# usb_light.net
KiCad netlist of a schematic drawn in EAGLE
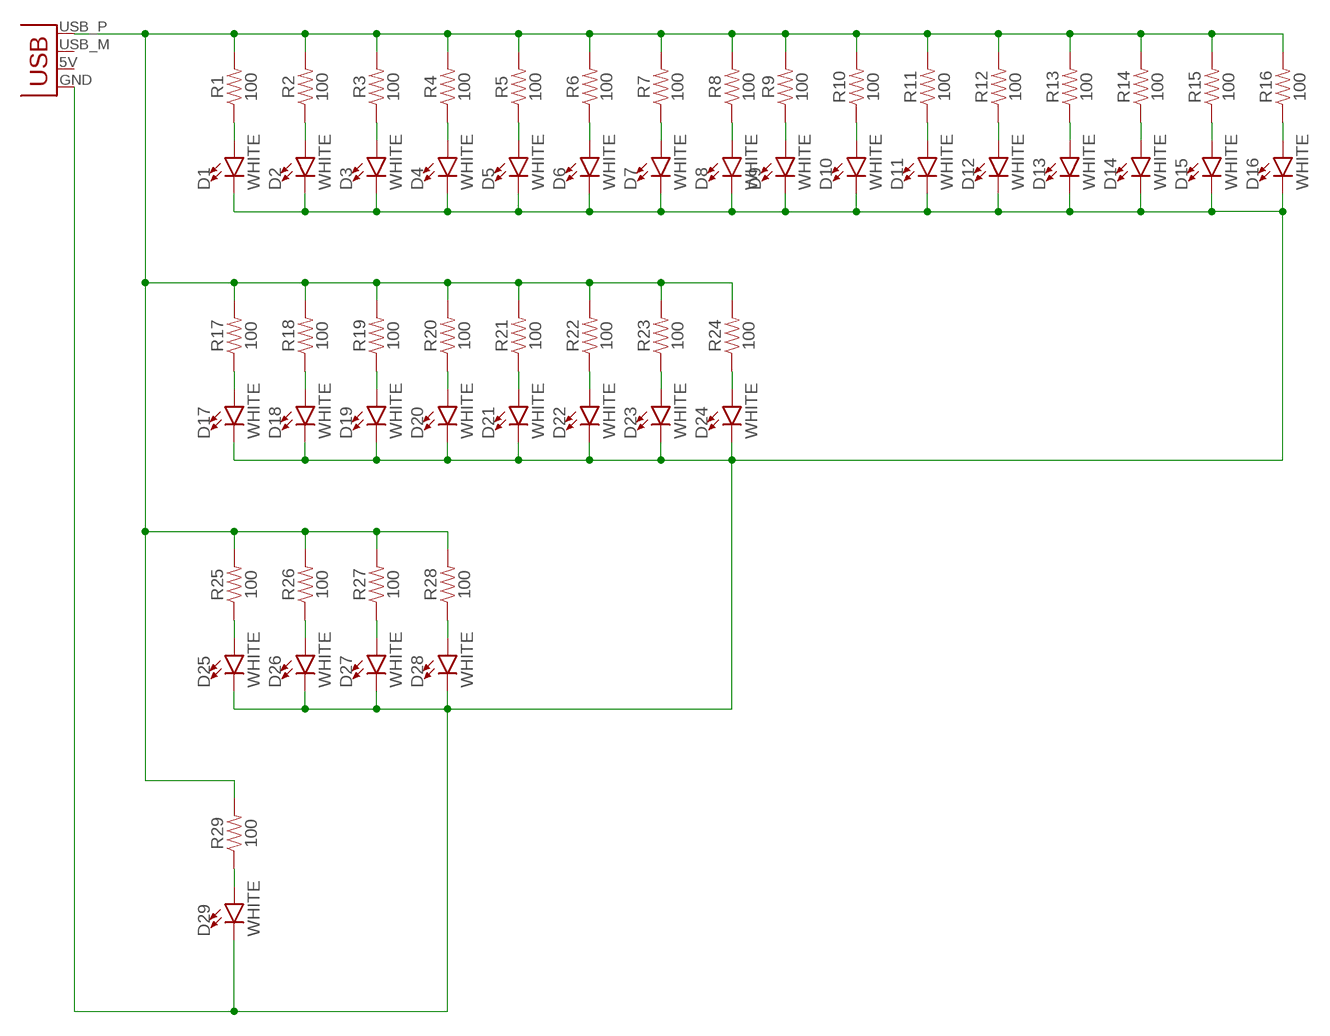
[diagram p0: schematic, sheet 1]

(export (version "E")
  (design (tool "Eeschema 10.0.6"))
  (components
    (comp (ref "D1")
      (value "WHITE")
      (footprint "eagle-import:LED-1206")
      (libsource (lib "eagle-import") (part "LED-WHITE1206"))
    )
    (comp (ref "D2")
      (value "WHITE")
      (footprint "eagle-import:LED-1206")
      (libsource (lib "eagle-import") (part "LED-WHITE1206"))
    )
    (comp (ref "D3")
      (value "WHITE")
      (footprint "eagle-import:LED-1206")
      (libsource (lib "eagle-import") (part "LED-WHITE1206"))
    )
    (comp (ref "D4")
      (value "WHITE")
      (footprint "eagle-import:LED-1206")
      (libsource (lib "eagle-import") (part "LED-WHITE1206"))
    )
    (comp (ref "D5")
      (value "WHITE")
      (footprint "eagle-import:LED-1206")
      (libsource (lib "eagle-import") (part "LED-WHITE1206"))
    )
    (comp (ref "D6")
      (value "WHITE")
      (footprint "eagle-import:LED-1206")
      (libsource (lib "eagle-import") (part "LED-WHITE1206"))
    )
    (comp (ref "D7")
      (value "WHITE")
      (footprint "eagle-import:LED-1206")
      (libsource (lib "eagle-import") (part "LED-WHITE1206"))
    )
    (comp (ref "D8")
      (value "WHITE")
      (footprint "eagle-import:LED-1206")
      (libsource (lib "eagle-import") (part "LED-WHITE1206"))
    )
    (comp (ref "D9")
      (value "WHITE")
      (footprint "eagle-import:LED-1206")
      (libsource (lib "eagle-import") (part "LED-WHITE1206"))
    )
    (comp (ref "D10")
      (value "WHITE")
      (footprint "eagle-import:LED-1206")
      (libsource (lib "eagle-import") (part "LED-WHITE1206"))
    )
    (comp (ref "D11")
      (value "WHITE")
      (footprint "eagle-import:LED-1206")
      (libsource (lib "eagle-import") (part "LED-WHITE1206"))
    )
    (comp (ref "D12")
      (value "WHITE")
      (footprint "eagle-import:LED-1206")
      (libsource (lib "eagle-import") (part "LED-WHITE1206"))
    )
    (comp (ref "D13")
      (value "WHITE")
      (footprint "eagle-import:LED-1206")
      (libsource (lib "eagle-import") (part "LED-WHITE1206"))
    )
    (comp (ref "D14")
      (value "WHITE")
      (footprint "eagle-import:LED-1206")
      (libsource (lib "eagle-import") (part "LED-WHITE1206"))
    )
    (comp (ref "D15")
      (value "WHITE")
      (footprint "eagle-import:LED-1206")
      (libsource (lib "eagle-import") (part "LED-WHITE1206"))
    )
    (comp (ref "D16")
      (value "WHITE")
      (footprint "eagle-import:LED-1206")
      (libsource (lib "eagle-import") (part "LED-WHITE1206"))
    )
    (comp (ref "D17")
      (value "WHITE")
      (footprint "eagle-import:LED-1206")
      (libsource (lib "eagle-import") (part "LED-WHITE1206"))
    )
    (comp (ref "D18")
      (value "WHITE")
      (footprint "eagle-import:LED-1206")
      (libsource (lib "eagle-import") (part "LED-WHITE1206"))
    )
    (comp (ref "D19")
      (value "WHITE")
      (footprint "eagle-import:LED-1206")
      (libsource (lib "eagle-import") (part "LED-WHITE1206"))
    )
    (comp (ref "D20")
      (value "WHITE")
      (footprint "eagle-import:LED-1206")
      (libsource (lib "eagle-import") (part "LED-WHITE1206"))
    )
    (comp (ref "D21")
      (value "WHITE")
      (footprint "eagle-import:LED-1206")
      (libsource (lib "eagle-import") (part "LED-WHITE1206"))
    )
    (comp (ref "D22")
      (value "WHITE")
      (footprint "eagle-import:LED-1206")
      (libsource (lib "eagle-import") (part "LED-WHITE1206"))
    )
    (comp (ref "D23")
      (value "WHITE")
      (footprint "eagle-import:LED-1206")
      (libsource (lib "eagle-import") (part "LED-WHITE1206"))
    )
    (comp (ref "D24")
      (value "WHITE")
      (footprint "eagle-import:LED-1206")
      (libsource (lib "eagle-import") (part "LED-WHITE1206"))
    )
    (comp (ref "D25")
      (value "WHITE")
      (footprint "eagle-import:LED-1206")
      (libsource (lib "eagle-import") (part "LED-WHITE1206"))
    )
    (comp (ref "D26")
      (value "WHITE")
      (footprint "eagle-import:LED-1206")
      (libsource (lib "eagle-import") (part "LED-WHITE1206"))
    )
    (comp (ref "D27")
      (value "WHITE")
      (footprint "eagle-import:LED-1206")
      (libsource (lib "eagle-import") (part "LED-WHITE1206"))
    )
    (comp (ref "D28")
      (value "WHITE")
      (footprint "eagle-import:LED-1206")
      (libsource (lib "eagle-import") (part "LED-WHITE1206"))
    )
    (comp (ref "D29")
      (value "WHITE")
      (footprint "eagle-import:LED-1206")
      (libsource (lib "eagle-import") (part "LED-WHITE1206"))
    )
    (comp (ref "R1")
      (value "100")
      (footprint "eagle-import:1206")
      (libsource (lib "eagle-import") (part "RESISTOR1206"))
    )
    (comp (ref "R2")
      (value "100")
      (footprint "eagle-import:1206")
      (libsource (lib "eagle-import") (part "RESISTOR1206"))
    )
    (comp (ref "R3")
      (value "100")
      (footprint "eagle-import:1206")
      (libsource (lib "eagle-import") (part "RESISTOR1206"))
    )
    (comp (ref "R4")
      (value "100")
      (footprint "eagle-import:1206")
      (libsource (lib "eagle-import") (part "RESISTOR1206"))
    )
    (comp (ref "R5")
      (value "100")
      (footprint "eagle-import:1206")
      (libsource (lib "eagle-import") (part "RESISTOR1206"))
    )
    (comp (ref "R6")
      (value "100")
      (footprint "eagle-import:1206")
      (libsource (lib "eagle-import") (part "RESISTOR1206"))
    )
    (comp (ref "R7")
      (value "100")
      (footprint "eagle-import:1206")
      (libsource (lib "eagle-import") (part "RESISTOR1206"))
    )
    (comp (ref "R8")
      (value "100")
      (footprint "eagle-import:1206")
      (libsource (lib "eagle-import") (part "RESISTOR1206"))
    )
    (comp (ref "R9")
      (value "100")
      (footprint "eagle-import:1206")
      (libsource (lib "eagle-import") (part "RESISTOR1206"))
    )
    (comp (ref "R10")
      (value "100")
      (footprint "eagle-import:1206")
      (libsource (lib "eagle-import") (part "RESISTOR1206"))
    )
    (comp (ref "R11")
      (value "100")
      (footprint "eagle-import:1206")
      (libsource (lib "eagle-import") (part "RESISTOR1206"))
    )
    (comp (ref "R12")
      (value "100")
      (footprint "eagle-import:1206")
      (libsource (lib "eagle-import") (part "RESISTOR1206"))
    )
    (comp (ref "R13")
      (value "100")
      (footprint "eagle-import:1206")
      (libsource (lib "eagle-import") (part "RESISTOR1206"))
    )
    (comp (ref "R14")
      (value "100")
      (footprint "eagle-import:1206")
      (libsource (lib "eagle-import") (part "RESISTOR1206"))
    )
    (comp (ref "R15")
      (value "100")
      (footprint "eagle-import:1206")
      (libsource (lib "eagle-import") (part "RESISTOR1206"))
    )
    (comp (ref "R16")
      (value "100")
      (footprint "eagle-import:1206")
      (libsource (lib "eagle-import") (part "RESISTOR1206"))
    )
    (comp (ref "R17")
      (value "100")
      (footprint "eagle-import:1206")
      (libsource (lib "eagle-import") (part "RESISTOR1206"))
    )
    (comp (ref "R18")
      (value "100")
      (footprint "eagle-import:1206")
      (libsource (lib "eagle-import") (part "RESISTOR1206"))
    )
    (comp (ref "R19")
      (value "100")
      (footprint "eagle-import:1206")
      (libsource (lib "eagle-import") (part "RESISTOR1206"))
    )
    (comp (ref "R20")
      (value "100")
      (footprint "eagle-import:1206")
      (libsource (lib "eagle-import") (part "RESISTOR1206"))
    )
    (comp (ref "R21")
      (value "100")
      (footprint "eagle-import:1206")
      (libsource (lib "eagle-import") (part "RESISTOR1206"))
    )
    (comp (ref "R22")
      (value "100")
      (footprint "eagle-import:1206")
      (libsource (lib "eagle-import") (part "RESISTOR1206"))
    )
    (comp (ref "R23")
      (value "100")
      (footprint "eagle-import:1206")
      (libsource (lib "eagle-import") (part "RESISTOR1206"))
    )
    (comp (ref "R24")
      (value "100")
      (footprint "eagle-import:1206")
      (libsource (lib "eagle-import") (part "RESISTOR1206"))
    )
    (comp (ref "R25")
      (value "100")
      (footprint "eagle-import:1206")
      (libsource (lib "eagle-import") (part "RESISTOR1206"))
    )
    (comp (ref "R26")
      (value "100")
      (footprint "eagle-import:1206")
      (libsource (lib "eagle-import") (part "RESISTOR1206"))
    )
    (comp (ref "R27")
      (value "100")
      (footprint "eagle-import:1206")
      (libsource (lib "eagle-import") (part "RESISTOR1206"))
    )
    (comp (ref "R28")
      (value "100")
      (footprint "eagle-import:1206")
      (libsource (lib "eagle-import") (part "RESISTOR1206"))
    )
    (comp (ref "R29")
      (value "100")
      (footprint "eagle-import:1206")
      (libsource (lib "eagle-import") (part "RESISTOR1206"))
    )
    (comp (ref "USB")
      (value "USBPCB")
      (footprint "eagle-import:USB-A-PCB")
      (libsource (lib "eagle-import") (part "USBPCB"))
    )
  )
  (nets
    (net (code "1") (name "Net-(D1-PadA)") (class "Default")
      (node (ref "D1") (pin "A") (pinfunction "A_A") (pintype "passive"))
      (node (ref "R1") (pin "1") (pinfunction "1_1") (pintype "passive"))
    )
    (net (code "2") (name "Net-(D1-PadC)") (class "Default")
      (node (ref "D1") (pin "C") (pinfunction "C_C") (pintype "passive"))
      (node (ref "D10") (pin "C") (pinfunction "C_C") (pintype "passive"))
      (node (ref "D11") (pin "C") (pinfunction "C_C") (pintype "passive"))
      (node (ref "D12") (pin "C") (pinfunction "C_C") (pintype "passive"))
      (node (ref "D13") (pin "C") (pinfunction "C_C") (pintype "passive"))
      (node (ref "D14") (pin "C") (pinfunction "C_C") (pintype "passive"))
      (node (ref "D15") (pin "C") (pinfunction "C_C") (pintype "passive"))
      (node (ref "D16") (pin "C") (pinfunction "C_C") (pintype "passive"))
      (node (ref "D17") (pin "C") (pinfunction "C_C") (pintype "passive"))
      (node (ref "D18") (pin "C") (pinfunction "C_C") (pintype "passive"))
      (node (ref "D19") (pin "C") (pinfunction "C_C") (pintype "passive"))
      (node (ref "D2") (pin "C") (pinfunction "C_C") (pintype "passive"))
      (node (ref "D20") (pin "C") (pinfunction "C_C") (pintype "passive"))
      (node (ref "D21") (pin "C") (pinfunction "C_C") (pintype "passive"))
      (node (ref "D22") (pin "C") (pinfunction "C_C") (pintype "passive"))
      (node (ref "D23") (pin "C") (pinfunction "C_C") (pintype "passive"))
      (node (ref "D24") (pin "C") (pinfunction "C_C") (pintype "passive"))
      (node (ref "D25") (pin "C") (pinfunction "C_C") (pintype "passive"))
      (node (ref "D26") (pin "C") (pinfunction "C_C") (pintype "passive"))
      (node (ref "D27") (pin "C") (pinfunction "C_C") (pintype "passive"))
      (node (ref "D28") (pin "C") (pinfunction "C_C") (pintype "passive"))
      (node (ref "D29") (pin "C") (pinfunction "C_C") (pintype "passive"))
      (node (ref "D3") (pin "C") (pinfunction "C_C") (pintype "passive"))
      (node (ref "D4") (pin "C") (pinfunction "C_C") (pintype "passive"))
      (node (ref "D5") (pin "C") (pinfunction "C_C") (pintype "passive"))
      (node (ref "D6") (pin "C") (pinfunction "C_C") (pintype "passive"))
      (node (ref "D7") (pin "C") (pinfunction "C_C") (pintype "passive"))
      (node (ref "D8") (pin "C") (pinfunction "C_C") (pintype "passive"))
      (node (ref "D9") (pin "C") (pinfunction "C_C") (pintype "passive"))
      (node (ref "USB") (pin "GND") (pinfunction "GND_GND") (pintype "bidirectional"))
    )
    (net (code "3") (name "Net-(D2-PadA)") (class "Default")
      (node (ref "D2") (pin "A") (pinfunction "A_A") (pintype "passive"))
      (node (ref "R2") (pin "1") (pinfunction "1_1") (pintype "passive"))
    )
    (net (code "4") (name "Net-(D3-PadA)") (class "Default")
      (node (ref "D3") (pin "A") (pinfunction "A_A") (pintype "passive"))
      (node (ref "R3") (pin "1") (pinfunction "1_1") (pintype "passive"))
    )
    (net (code "5") (name "Net-(D4-PadA)") (class "Default")
      (node (ref "D4") (pin "A") (pinfunction "A_A") (pintype "passive"))
      (node (ref "R4") (pin "1") (pinfunction "1_1") (pintype "passive"))
    )
    (net (code "6") (name "Net-(D5-PadA)") (class "Default")
      (node (ref "D5") (pin "A") (pinfunction "A_A") (pintype "passive"))
      (node (ref "R5") (pin "1") (pinfunction "1_1") (pintype "passive"))
    )
    (net (code "7") (name "Net-(D6-PadA)") (class "Default")
      (node (ref "D6") (pin "A") (pinfunction "A_A") (pintype "passive"))
      (node (ref "R6") (pin "1") (pinfunction "1_1") (pintype "passive"))
    )
    (net (code "8") (name "Net-(D7-PadA)") (class "Default")
      (node (ref "D7") (pin "A") (pinfunction "A_A") (pintype "passive"))
      (node (ref "R7") (pin "1") (pinfunction "1_1") (pintype "passive"))
    )
    (net (code "9") (name "Net-(D8-PadA)") (class "Default")
      (node (ref "D8") (pin "A") (pinfunction "A_A") (pintype "passive"))
      (node (ref "R8") (pin "1") (pinfunction "1_1") (pintype "passive"))
    )
    (net (code "10") (name "Net-(D9-PadA)") (class "Default")
      (node (ref "D9") (pin "A") (pinfunction "A_A") (pintype "passive"))
      (node (ref "R9") (pin "1") (pinfunction "1_1") (pintype "passive"))
    )
    (net (code "11") (name "Net-(D10-PadA)") (class "Default")
      (node (ref "D10") (pin "A") (pinfunction "A_A") (pintype "passive"))
      (node (ref "R10") (pin "1") (pinfunction "1_1") (pintype "passive"))
    )
    (net (code "12") (name "Net-(D11-PadA)") (class "Default")
      (node (ref "D11") (pin "A") (pinfunction "A_A") (pintype "passive"))
      (node (ref "R11") (pin "1") (pinfunction "1_1") (pintype "passive"))
    )
    (net (code "13") (name "Net-(D12-PadA)") (class "Default")
      (node (ref "D12") (pin "A") (pinfunction "A_A") (pintype "passive"))
      (node (ref "R12") (pin "1") (pinfunction "1_1") (pintype "passive"))
    )
    (net (code "14") (name "Net-(D13-PadA)") (class "Default")
      (node (ref "D13") (pin "A") (pinfunction "A_A") (pintype "passive"))
      (node (ref "R13") (pin "1") (pinfunction "1_1") (pintype "passive"))
    )
    (net (code "15") (name "Net-(D14-PadA)") (class "Default")
      (node (ref "D14") (pin "A") (pinfunction "A_A") (pintype "passive"))
      (node (ref "R14") (pin "1") (pinfunction "1_1") (pintype "passive"))
    )
    (net (code "16") (name "Net-(D15-PadA)") (class "Default")
      (node (ref "D15") (pin "A") (pinfunction "A_A") (pintype "passive"))
      (node (ref "R15") (pin "1") (pinfunction "1_1") (pintype "passive"))
    )
    (net (code "17") (name "Net-(D16-PadA)") (class "Default")
      (node (ref "D16") (pin "A") (pinfunction "A_A") (pintype "passive"))
      (node (ref "R16") (pin "1") (pinfunction "1_1") (pintype "passive"))
    )
    (net (code "18") (name "Net-(D17-PadA)") (class "Default")
      (node (ref "D17") (pin "A") (pinfunction "A_A") (pintype "passive"))
      (node (ref "R17") (pin "1") (pinfunction "1_1") (pintype "passive"))
    )
    (net (code "19") (name "Net-(D18-PadA)") (class "Default")
      (node (ref "D18") (pin "A") (pinfunction "A_A") (pintype "passive"))
      (node (ref "R18") (pin "1") (pinfunction "1_1") (pintype "passive"))
    )
    (net (code "20") (name "Net-(D19-PadA)") (class "Default")
      (node (ref "D19") (pin "A") (pinfunction "A_A") (pintype "passive"))
      (node (ref "R19") (pin "1") (pinfunction "1_1") (pintype "passive"))
    )
    (net (code "21") (name "Net-(D20-PadA)") (class "Default")
      (node (ref "D20") (pin "A") (pinfunction "A_A") (pintype "passive"))
      (node (ref "R20") (pin "1") (pinfunction "1_1") (pintype "passive"))
    )
    (net (code "22") (name "Net-(D21-PadA)") (class "Default")
      (node (ref "D21") (pin "A") (pinfunction "A_A") (pintype "passive"))
      (node (ref "R21") (pin "1") (pinfunction "1_1") (pintype "passive"))
    )
    (net (code "23") (name "Net-(D22-PadA)") (class "Default")
      (node (ref "D22") (pin "A") (pinfunction "A_A") (pintype "passive"))
      (node (ref "R22") (pin "1") (pinfunction "1_1") (pintype "passive"))
    )
    (net (code "24") (name "Net-(D23-PadA)") (class "Default")
      (node (ref "D23") (pin "A") (pinfunction "A_A") (pintype "passive"))
      (node (ref "R23") (pin "1") (pinfunction "1_1") (pintype "passive"))
    )
    (net (code "25") (name "Net-(D24-PadA)") (class "Default")
      (node (ref "D24") (pin "A") (pinfunction "A_A") (pintype "passive"))
      (node (ref "R24") (pin "1") (pinfunction "1_1") (pintype "passive"))
    )
    (net (code "26") (name "Net-(D25-PadA)") (class "Default")
      (node (ref "D25") (pin "A") (pinfunction "A_A") (pintype "passive"))
      (node (ref "R25") (pin "1") (pinfunction "1_1") (pintype "passive"))
    )
    (net (code "27") (name "Net-(D26-PadA)") (class "Default")
      (node (ref "D26") (pin "A") (pinfunction "A_A") (pintype "passive"))
      (node (ref "R26") (pin "1") (pinfunction "1_1") (pintype "passive"))
    )
    (net (code "28") (name "Net-(D27-PadA)") (class "Default")
      (node (ref "D27") (pin "A") (pinfunction "A_A") (pintype "passive"))
      (node (ref "R27") (pin "1") (pinfunction "1_1") (pintype "passive"))
    )
    (net (code "29") (name "Net-(D28-PadA)") (class "Default")
      (node (ref "D28") (pin "A") (pinfunction "A_A") (pintype "passive"))
      (node (ref "R28") (pin "1") (pinfunction "1_1") (pintype "passive"))
    )
    (net (code "30") (name "Net-(D29-PadA)") (class "Default")
      (node (ref "D29") (pin "A") (pinfunction "A_A") (pintype "passive"))
      (node (ref "R29") (pin "1") (pinfunction "1_1") (pintype "passive"))
    )
    (net (code "31") (name "Net-(USB-D+)") (class "Default")
      (node (ref "R1") (pin "2") (pinfunction "2_2") (pintype "passive"))
      (node (ref "R10") (pin "2") (pinfunction "2_2") (pintype "passive"))
      (node (ref "R11") (pin "2") (pinfunction "2_2") (pintype "passive"))
      (node (ref "R12") (pin "2") (pinfunction "2_2") (pintype "passive"))
      (node (ref "R13") (pin "2") (pinfunction "2_2") (pintype "passive"))
      (node (ref "R14") (pin "2") (pinfunction "2_2") (pintype "passive"))
      (node (ref "R15") (pin "2") (pinfunction "2_2") (pintype "passive"))
      (node (ref "R16") (pin "2") (pinfunction "2_2") (pintype "passive"))
      (node (ref "R17") (pin "2") (pinfunction "2_2") (pintype "passive"))
      (node (ref "R18") (pin "2") (pinfunction "2_2") (pintype "passive"))
      (node (ref "R19") (pin "2") (pinfunction "2_2") (pintype "passive"))
      (node (ref "R2") (pin "2") (pinfunction "2_2") (pintype "passive"))
      (node (ref "R20") (pin "2") (pinfunction "2_2") (pintype "passive"))
      (node (ref "R21") (pin "2") (pinfunction "2_2") (pintype "passive"))
      (node (ref "R22") (pin "2") (pinfunction "2_2") (pintype "passive"))
      (node (ref "R23") (pin "2") (pinfunction "2_2") (pintype "passive"))
      (node (ref "R24") (pin "2") (pinfunction "2_2") (pintype "passive"))
      (node (ref "R25") (pin "2") (pinfunction "2_2") (pintype "passive"))
      (node (ref "R26") (pin "2") (pinfunction "2_2") (pintype "passive"))
      (node (ref "R27") (pin "2") (pinfunction "2_2") (pintype "passive"))
      (node (ref "R28") (pin "2") (pinfunction "2_2") (pintype "passive"))
      (node (ref "R29") (pin "2") (pinfunction "2_2") (pintype "passive"))
      (node (ref "R3") (pin "2") (pinfunction "2_2") (pintype "passive"))
      (node (ref "R4") (pin "2") (pinfunction "2_2") (pintype "passive"))
      (node (ref "R5") (pin "2") (pinfunction "2_2") (pintype "passive"))
      (node (ref "R6") (pin "2") (pinfunction "2_2") (pintype "passive"))
      (node (ref "R7") (pin "2") (pinfunction "2_2") (pintype "passive"))
      (node (ref "R8") (pin "2") (pinfunction "2_2") (pintype "passive"))
      (node (ref "R9") (pin "2") (pinfunction "2_2") (pintype "passive"))
      (node (ref "USB") (pin "USB_P") (pinfunction "D+_USB_P") (pintype "bidirectional"))
    )
    (net (code "32") (name "unconnected-(USB-D--PadUSB_M)") (class "Default")
      (node (ref "USB") (pin "USB_M") (pinfunction "D-_USB_M") (pintype "bidirectional"))
    )
    (net (code "33") (name "unconnected-(USB-VBUS-Pad5V)") (class "Default")
      (node (ref "USB") (pin "5V") (pinfunction "VBUS_5V") (pintype "bidirectional"))
    )
  )
)
